# FPGA-Blitter.net
KiCad netlist of a schematic drawn in EAGLE
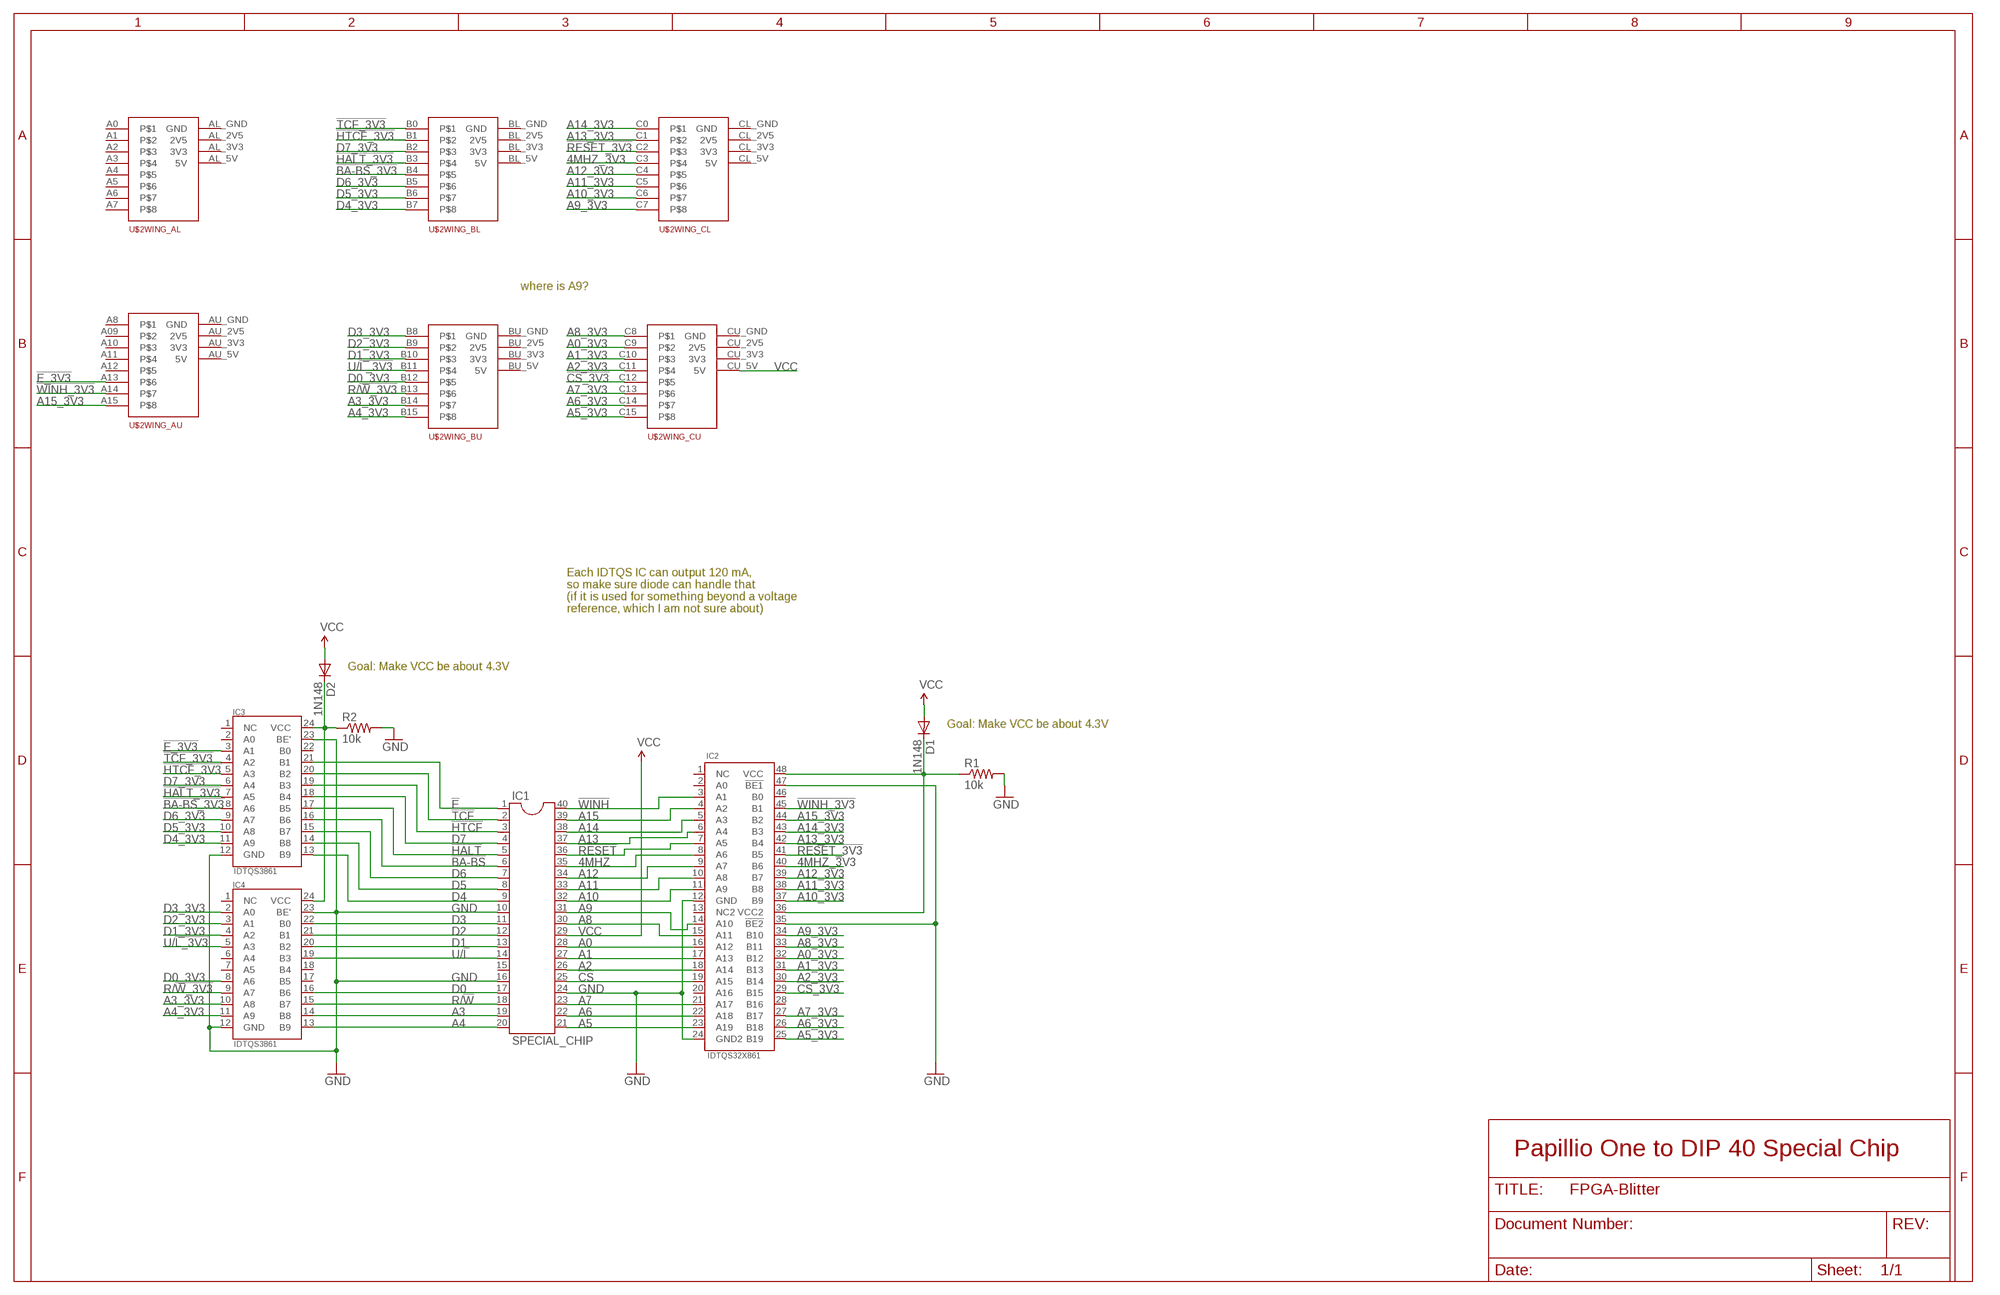
[diagram p0: schematic, sheet 1]

(export (version "E")
  (design (tool "Eeschema 10.0.6"))
  (components
    (comp (ref "D1")
      (value "1N148")
      (footprint "eagle-import:DIODE-1N4148")
      (libsource (lib "eagle-import") (part "DIODE1N4148"))
    )
    (comp (ref "D2")
      (value "1N148")
      (footprint "eagle-import:DIODE-1N4148")
      (libsource (lib "eagle-import") (part "DIODE1N4148"))
    )
    (comp (ref "IC1")
      (value "SPECIAL_CHIP")
      (footprint "eagle-import:DIL40")
      (libsource (lib "eagle-import") (part "DIL40"))
    )
    (comp (ref "IC2")
      (value "IDTQS32X861")
      (footprint "eagle-import:QVSOP-DJG48-IDT")
      (libsource (lib "eagle-import") (part "IDTQS32X861"))
    )
    (comp (ref "IC3")
      (value "IDTQS3861")
      (footprint "eagle-import:TSSOP24")
      (libsource (lib "eagle-import") (part "IDTQS3861"))
    )
    (comp (ref "IC4")
      (value "IDTQS3861")
      (footprint "eagle-import:TSSOP24")
      (libsource (lib "eagle-import") (part "IDTQS3861"))
    )
    (comp (ref "R1")
      (value "10k")
      (footprint "eagle-import:1206")
      (libsource (lib "eagle-import") (part "RESISTOR1206"))
    )
    (comp (ref "R2")
      (value "10k")
      (footprint "eagle-import:1206")
      (libsource (lib "eagle-import") (part "RESISTOR1206"))
    )
    (comp (ref "U$2")
      (value "PAPILIO48")
      (footprint "eagle-import:PAPILIO48")
      (libsource (lib "eagle-import") (part "PAPILIO48"))
    )
  )
  (nets
    (net (code "1") (name "/4MHZ") (class "Default")
      (node (ref "IC1") (pin "35") (pinfunction "35_35") (pintype "passive"))
      (node (ref "IC2") (pin "8") (pinfunction "A6_8") (pintype "bidirectional"))
    )
    (net (code "2") (name "/4MHZ_3V3") (class "Default")
      (node (ref "IC2") (pin "40") (pinfunction "B6_40") (pintype "bidirectional"))
      (node (ref "U$2") (pin "C3") (pinfunction "P$4_C3") (pintype "bidirectional"))
    )
    (net (code "3") (name "/A0") (class "Default")
      (node (ref "IC1") (pin "28") (pinfunction "28_28") (pintype "passive"))
      (node (ref "IC2") (pin "16") (pinfunction "A12_16") (pintype "bidirectional"))
    )
    (net (code "4") (name "/A0_3V3") (class "Default")
      (node (ref "IC2") (pin "32") (pinfunction "B12_32") (pintype "bidirectional"))
      (node (ref "U$2") (pin "C9") (pinfunction "P$2_C9") (pintype "bidirectional"))
    )
    (net (code "5") (name "/A1") (class "Default")
      (node (ref "IC1") (pin "27") (pinfunction "27_27") (pintype "passive"))
      (node (ref "IC2") (pin "17") (pinfunction "A13_17") (pintype "bidirectional"))
    )
    (net (code "6") (name "/A1_3V3") (class "Default")
      (node (ref "IC2") (pin "31") (pinfunction "B13_31") (pintype "bidirectional"))
      (node (ref "U$2") (pin "C10") (pinfunction "P$3_C10") (pintype "bidirectional"))
    )
    (net (code "7") (name "/A2") (class "Default")
      (node (ref "IC1") (pin "26") (pinfunction "26_26") (pintype "passive"))
      (node (ref "IC2") (pin "18") (pinfunction "A14_18") (pintype "bidirectional"))
    )
    (net (code "8") (name "/A2_3V3") (class "Default")
      (node (ref "IC2") (pin "30") (pinfunction "B14_30") (pintype "bidirectional"))
      (node (ref "U$2") (pin "C11") (pinfunction "P$4_C11") (pintype "bidirectional"))
    )
    (net (code "9") (name "/A3") (class "Default")
      (node (ref "IC1") (pin "19") (pinfunction "19_19") (pintype "passive"))
      (node (ref "IC4") (pin "14") (pinfunction "B8_14") (pintype "bidirectional"))
    )
    (net (code "10") (name "/A3_3V3") (class "Default")
      (node (ref "IC4") (pin "10") (pinfunction "A8_10") (pintype "bidirectional"))
      (node (ref "U$2") (pin "B14") (pinfunction "P$7_B14") (pintype "bidirectional"))
    )
    (net (code "11") (name "/A4") (class "Default")
      (node (ref "IC1") (pin "20") (pinfunction "20_20") (pintype "passive"))
      (node (ref "IC4") (pin "13") (pinfunction "B9_13") (pintype "bidirectional"))
    )
    (net (code "12") (name "/A4_3V3") (class "Default")
      (node (ref "IC4") (pin "11") (pinfunction "A9_11") (pintype "bidirectional"))
      (node (ref "U$2") (pin "B15") (pinfunction "P$8_B15") (pintype "bidirectional"))
    )
    (net (code "13") (name "/A5") (class "Default")
      (node (ref "IC1") (pin "21") (pinfunction "21_21") (pintype "passive"))
      (node (ref "IC2") (pin "23") (pinfunction "A19_23") (pintype "bidirectional"))
    )
    (net (code "14") (name "/A5_3V3") (class "Default")
      (node (ref "IC2") (pin "25") (pinfunction "B19_25") (pintype "bidirectional"))
      (node (ref "U$2") (pin "C15") (pinfunction "P$8_C15") (pintype "bidirectional"))
    )
    (net (code "15") (name "/A6") (class "Default")
      (node (ref "IC1") (pin "22") (pinfunction "22_22") (pintype "passive"))
      (node (ref "IC2") (pin "22") (pinfunction "A18_22") (pintype "bidirectional"))
    )
    (net (code "16") (name "/A6_3V3") (class "Default")
      (node (ref "IC2") (pin "26") (pinfunction "B18_26") (pintype "bidirectional"))
      (node (ref "U$2") (pin "C14") (pinfunction "P$7_C14") (pintype "bidirectional"))
    )
    (net (code "17") (name "/A7") (class "Default")
      (node (ref "IC1") (pin "23") (pinfunction "23_23") (pintype "passive"))
      (node (ref "IC2") (pin "21") (pinfunction "A17_21") (pintype "bidirectional"))
    )
    (net (code "18") (name "/A7_3V3") (class "Default")
      (node (ref "IC2") (pin "27") (pinfunction "B17_27") (pintype "bidirectional"))
      (node (ref "U$2") (pin "C13") (pinfunction "P$6_C13") (pintype "bidirectional"))
    )
    (net (code "19") (name "/A8") (class "Default")
      (node (ref "IC1") (pin "30") (pinfunction "30_30") (pintype "passive"))
      (node (ref "IC2") (pin "15") (pinfunction "A11_15") (pintype "bidirectional"))
    )
    (net (code "20") (name "/A8_3V3") (class "Default")
      (node (ref "IC2") (pin "33") (pinfunction "B11_33") (pintype "bidirectional"))
      (node (ref "U$2") (pin "C8") (pinfunction "P$1_C8") (pintype "bidirectional"))
    )
    (net (code "21") (name "/A9") (class "Default")
      (node (ref "IC1") (pin "31") (pinfunction "31_31") (pintype "passive"))
      (node (ref "IC2") (pin "14") (pinfunction "A10_14") (pintype "bidirectional"))
    )
    (net (code "22") (name "/A9_3V3") (class "Default")
      (node (ref "IC2") (pin "34") (pinfunction "B10_34") (pintype "bidirectional"))
      (node (ref "U$2") (pin "C7") (pinfunction "P$8_C7") (pintype "bidirectional"))
    )
    (net (code "23") (name "/A10") (class "Default")
      (node (ref "IC1") (pin "32") (pinfunction "32_32") (pintype "passive"))
      (node (ref "IC2") (pin "11") (pinfunction "A9_11") (pintype "bidirectional"))
    )
    (net (code "24") (name "/A10_3V3") (class "Default")
      (node (ref "IC2") (pin "37") (pinfunction "B9_37") (pintype "bidirectional"))
      (node (ref "U$2") (pin "C6") (pinfunction "P$7_C6") (pintype "bidirectional"))
    )
    (net (code "25") (name "/A11") (class "Default")
      (node (ref "IC1") (pin "33") (pinfunction "33_33") (pintype "passive"))
      (node (ref "IC2") (pin "10") (pinfunction "A8_10") (pintype "bidirectional"))
    )
    (net (code "26") (name "/A11_3V3") (class "Default")
      (node (ref "IC2") (pin "38") (pinfunction "B8_38") (pintype "bidirectional"))
      (node (ref "U$2") (pin "C5") (pinfunction "P$6_C5") (pintype "bidirectional"))
    )
    (net (code "27") (name "/A12") (class "Default")
      (node (ref "IC1") (pin "34") (pinfunction "34_34") (pintype "passive"))
      (node (ref "IC2") (pin "9") (pinfunction "A7_9") (pintype "bidirectional"))
    )
    (net (code "28") (name "/A12_3V3") (class "Default")
      (node (ref "IC2") (pin "39") (pinfunction "B7_39") (pintype "bidirectional"))
      (node (ref "U$2") (pin "C4") (pinfunction "P$5_C4") (pintype "bidirectional"))
    )
    (net (code "29") (name "/A13") (class "Default")
      (node (ref "IC1") (pin "37") (pinfunction "37_37") (pintype "passive"))
      (node (ref "IC2") (pin "6") (pinfunction "A4_6") (pintype "bidirectional"))
    )
    (net (code "30") (name "/A13_3V3") (class "Default")
      (node (ref "IC2") (pin "42") (pinfunction "B4_42") (pintype "bidirectional"))
      (node (ref "U$2") (pin "C1") (pinfunction "P$2_C1") (pintype "bidirectional"))
    )
    (net (code "31") (name "/A14") (class "Default")
      (node (ref "IC1") (pin "38") (pinfunction "38_38") (pintype "passive"))
      (node (ref "IC2") (pin "5") (pinfunction "A3_5") (pintype "bidirectional"))
    )
    (net (code "32") (name "/A14_3V3") (class "Default")
      (node (ref "IC2") (pin "43") (pinfunction "B3_43") (pintype "bidirectional"))
      (node (ref "U$2") (pin "C0") (pinfunction "P$1_C0") (pintype "bidirectional"))
    )
    (net (code "33") (name "/A15") (class "Default")
      (node (ref "IC1") (pin "39") (pinfunction "39_39") (pintype "passive"))
      (node (ref "IC2") (pin "4") (pinfunction "A2_4") (pintype "bidirectional"))
    )
    (net (code "34") (name "/A15_3V3") (class "Default")
      (node (ref "IC2") (pin "44") (pinfunction "B2_44") (pintype "bidirectional"))
      (node (ref "U$2") (pin "A15") (pinfunction "P$8_A15") (pintype "bidirectional"))
    )
    (net (code "35") (name "/D0") (class "Default")
      (node (ref "IC1") (pin "17") (pinfunction "17_17") (pintype "passive"))
      (node (ref "IC4") (pin "16") (pinfunction "B6_16") (pintype "bidirectional"))
    )
    (net (code "36") (name "/D0_3V3") (class "Default")
      (node (ref "IC4") (pin "8") (pinfunction "A6_8") (pintype "bidirectional"))
      (node (ref "U$2") (pin "B12") (pinfunction "P$5_B12") (pintype "bidirectional"))
    )
    (net (code "37") (name "/D1") (class "Default")
      (node (ref "IC1") (pin "13") (pinfunction "13_13") (pintype "passive"))
      (node (ref "IC4") (pin "20") (pinfunction "B2_20") (pintype "bidirectional"))
    )
    (net (code "38") (name "/D1_3V3") (class "Default")
      (node (ref "IC4") (pin "4") (pinfunction "A2_4") (pintype "bidirectional"))
      (node (ref "U$2") (pin "B10") (pinfunction "P$3_B10") (pintype "bidirectional"))
    )
    (net (code "39") (name "/D2") (class "Default")
      (node (ref "IC1") (pin "12") (pinfunction "12_12") (pintype "passive"))
      (node (ref "IC4") (pin "21") (pinfunction "B1_21") (pintype "bidirectional"))
    )
    (net (code "40") (name "/D2_3V3") (class "Default")
      (node (ref "IC4") (pin "3") (pinfunction "A1_3") (pintype "bidirectional"))
      (node (ref "U$2") (pin "B9") (pinfunction "P$2_B9") (pintype "bidirectional"))
    )
    (net (code "41") (name "/D3") (class "Default")
      (node (ref "IC1") (pin "11") (pinfunction "11_11") (pintype "passive"))
      (node (ref "IC4") (pin "22") (pinfunction "B0_22") (pintype "bidirectional"))
    )
    (net (code "42") (name "/D3_3V3") (class "Default")
      (node (ref "IC4") (pin "2") (pinfunction "A0_2") (pintype "bidirectional"))
      (node (ref "U$2") (pin "B8") (pinfunction "P$1_B8") (pintype "bidirectional"))
    )
    (net (code "43") (name "/D4") (class "Default")
      (node (ref "IC1") (pin "9") (pinfunction "9_9") (pintype "passive"))
      (node (ref "IC3") (pin "13") (pinfunction "B9_13") (pintype "bidirectional"))
    )
    (net (code "44") (name "/D4_3V3") (class "Default")
      (node (ref "IC3") (pin "11") (pinfunction "A9_11") (pintype "bidirectional"))
      (node (ref "U$2") (pin "B7") (pinfunction "P$8_B7") (pintype "bidirectional"))
    )
    (net (code "45") (name "/D5") (class "Default")
      (node (ref "IC1") (pin "8") (pinfunction "8_8") (pintype "passive"))
      (node (ref "IC3") (pin "14") (pinfunction "B8_14") (pintype "bidirectional"))
    )
    (net (code "46") (name "/D5_3V3") (class "Default")
      (node (ref "IC3") (pin "10") (pinfunction "A8_10") (pintype "bidirectional"))
      (node (ref "U$2") (pin "B6") (pinfunction "P$7_B6") (pintype "bidirectional"))
    )
    (net (code "47") (name "/D6") (class "Default")
      (node (ref "IC1") (pin "7") (pinfunction "7_7") (pintype "passive"))
      (node (ref "IC3") (pin "15") (pinfunction "B7_15") (pintype "bidirectional"))
    )
    (net (code "48") (name "/D6_3V3") (class "Default")
      (node (ref "IC3") (pin "9") (pinfunction "A7_9") (pintype "bidirectional"))
      (node (ref "U$2") (pin "B5") (pinfunction "P$6_B5") (pintype "bidirectional"))
    )
    (net (code "49") (name "/D7") (class "Default")
      (node (ref "IC1") (pin "4") (pinfunction "4_4") (pintype "passive"))
      (node (ref "IC3") (pin "18") (pinfunction "B4_18") (pintype "bidirectional"))
    )
    (net (code "50") (name "/D7_3V3") (class "Default")
      (node (ref "IC3") (pin "6") (pinfunction "A4_6") (pintype "bidirectional"))
      (node (ref "U$2") (pin "B2") (pinfunction "P$3_B2") (pintype "bidirectional"))
    )
    (net (code "51") (name "/R{slash}~{W_3V3}") (class "Default")
      (node (ref "IC4") (pin "9") (pinfunction "A7_9") (pintype "bidirectional"))
      (node (ref "U$2") (pin "B13") (pinfunction "P$6_B13") (pintype "bidirectional"))
    )
    (net (code "52") (name "/R{slash}~{W}") (class "Default")
      (node (ref "IC1") (pin "18") (pinfunction "18_18") (pintype "passive"))
      (node (ref "IC4") (pin "15") (pinfunction "B7_15") (pintype "bidirectional"))
    )
    (net (code "53") (name "/U{slash}~{L_3V3}") (class "Default")
      (node (ref "IC4") (pin "5") (pinfunction "A3_5") (pintype "bidirectional"))
      (node (ref "U$2") (pin "B11") (pinfunction "P$4_B11") (pintype "bidirectional"))
    )
    (net (code "54") (name "/U{slash}~{L}") (class "Default")
      (node (ref "IC1") (pin "14") (pinfunction "14_14") (pintype "passive"))
      (node (ref "IC4") (pin "19") (pinfunction "B3_19") (pintype "bidirectional"))
    )
    (net (code "55") (name "/~{BA-BS_3V3}") (class "Default")
      (node (ref "IC3") (pin "8") (pinfunction "A6_8") (pintype "bidirectional"))
      (node (ref "U$2") (pin "B4") (pinfunction "P$5_B4") (pintype "bidirectional"))
    )
    (net (code "56") (name "/~{BA-BS}") (class "Default")
      (node (ref "IC1") (pin "6") (pinfunction "6_6") (pintype "passive"))
      (node (ref "IC3") (pin "16") (pinfunction "B6_16") (pintype "bidirectional"))
    )
    (net (code "57") (name "/~{CS_3V3}") (class "Default")
      (node (ref "IC2") (pin "29") (pinfunction "B15_29") (pintype "bidirectional"))
      (node (ref "U$2") (pin "C12") (pinfunction "P$5_C12") (pintype "bidirectional"))
    )
    (net (code "58") (name "/~{CS}") (class "Default")
      (node (ref "IC1") (pin "25") (pinfunction "25_25") (pintype "passive"))
      (node (ref "IC2") (pin "19") (pinfunction "A15_19") (pintype "bidirectional"))
    )
    (net (code "59") (name "/~{E_3V3}") (class "Default")
      (node (ref "IC3") (pin "3") (pinfunction "A1_3") (pintype "bidirectional"))
      (node (ref "U$2") (pin "A13") (pinfunction "P$6_A13") (pintype "bidirectional"))
    )
    (net (code "60") (name "/~{E}") (class "Default")
      (node (ref "IC1") (pin "1") (pinfunction "1_1") (pintype "passive"))
      (node (ref "IC3") (pin "21") (pinfunction "B1_21") (pintype "bidirectional"))
    )
    (net (code "61") (name "/~{HALT_3V3}") (class "Default")
      (node (ref "IC3") (pin "7") (pinfunction "A5_7") (pintype "bidirectional"))
      (node (ref "U$2") (pin "B3") (pinfunction "P$4_B3") (pintype "bidirectional"))
    )
    (net (code "62") (name "/~{HALT}") (class "Default")
      (node (ref "IC1") (pin "5") (pinfunction "5_5") (pintype "passive"))
      (node (ref "IC3") (pin "17") (pinfunction "B5_17") (pintype "bidirectional"))
    )
    (net (code "63") (name "/~{HTCF_3V3}") (class "Default")
      (node (ref "IC3") (pin "5") (pinfunction "A3_5") (pintype "bidirectional"))
      (node (ref "U$2") (pin "B1") (pinfunction "P$2_B1") (pintype "bidirectional"))
    )
    (net (code "64") (name "/~{HTCF}") (class "Default")
      (node (ref "IC1") (pin "3") (pinfunction "3_3") (pintype "passive"))
      (node (ref "IC3") (pin "19") (pinfunction "B3_19") (pintype "bidirectional"))
    )
    (net (code "65") (name "/~{RESET_3V3}") (class "Default")
      (node (ref "IC2") (pin "41") (pinfunction "B5_41") (pintype "bidirectional"))
      (node (ref "U$2") (pin "C2") (pinfunction "P$3_C2") (pintype "bidirectional"))
    )
    (net (code "66") (name "/~{RESET}") (class "Default")
      (node (ref "IC1") (pin "36") (pinfunction "36_36") (pintype "passive"))
      (node (ref "IC2") (pin "7") (pinfunction "A5_7") (pintype "bidirectional"))
    )
    (net (code "67") (name "/~{TCF_3V3}") (class "Default")
      (node (ref "IC3") (pin "4") (pinfunction "A2_4") (pintype "bidirectional"))
      (node (ref "U$2") (pin "B0") (pinfunction "P$1_B0") (pintype "bidirectional"))
    )
    (net (code "68") (name "/~{TCF}") (class "Default")
      (node (ref "IC1") (pin "2") (pinfunction "2_2") (pintype "passive"))
      (node (ref "IC3") (pin "20") (pinfunction "B2_20") (pintype "bidirectional"))
    )
    (net (code "69") (name "/~{WINH_3V3}") (class "Default")
      (node (ref "IC2") (pin "45") (pinfunction "B1_45") (pintype "bidirectional"))
      (node (ref "U$2") (pin "A14") (pinfunction "P$7_A14") (pintype "bidirectional"))
    )
    (net (code "70") (name "/~{WINH}") (class "Default")
      (node (ref "IC1") (pin "40") (pinfunction "40_40") (pintype "passive"))
      (node (ref "IC2") (pin "3") (pinfunction "A1_3") (pintype "bidirectional"))
    )
    (net (code "71") (name "GND") (class "Default")
      (node (ref "IC1") (pin "10") (pinfunction "10_10") (pintype "passive"))
      (node (ref "IC1") (pin "16") (pinfunction "16_16") (pintype "passive"))
      (node (ref "IC1") (pin "24") (pinfunction "24_24") (pintype "passive"))
      (node (ref "IC2") (pin "12") (pinfunction "GND_12") (pintype "bidirectional"))
      (node (ref "IC2") (pin "24") (pinfunction "GND2_24") (pintype "bidirectional"))
      (node (ref "IC2") (pin "35") (pinfunction "~{BE2}_35") (pintype "bidirectional"))
      (node (ref "IC2") (pin "47") (pinfunction "~{BE1}_47") (pintype "bidirectional"))
      (node (ref "IC3") (pin "12") (pinfunction "GND_12") (pintype "bidirectional"))
      (node (ref "IC3") (pin "23") (pinfunction "BE'_23") (pintype "bidirectional"))
      (node (ref "IC4") (pin "12") (pinfunction "GND_12") (pintype "bidirectional"))
      (node (ref "IC4") (pin "23") (pinfunction "BE'_23") (pintype "bidirectional"))
      (node (ref "R1") (pin "2") (pinfunction "2_2") (pintype "passive"))
      (node (ref "R2") (pin "2") (pinfunction "2_2") (pintype "passive"))
    )
    (net (code "72") (name "Net-(IC2-VCC)") (class "Default")
      (node (ref "D1") (pin "C") (pinfunction "C_C") (pintype "passive"))
      (node (ref "IC2") (pin "36") (pinfunction "VCC2_36") (pintype "bidirectional"))
      (node (ref "IC2") (pin "48") (pinfunction "VCC_48") (pintype "bidirectional"))
      (node (ref "R1") (pin "1") (pinfunction "1_1") (pintype "passive"))
    )
    (net (code "73") (name "Net-(IC3-VCC)") (class "Default")
      (node (ref "D2") (pin "C") (pinfunction "C_C") (pintype "passive"))
      (node (ref "IC3") (pin "24") (pinfunction "VCC_24") (pintype "bidirectional"))
      (node (ref "IC4") (pin "24") (pinfunction "VCC_24") (pintype "bidirectional"))
      (node (ref "R2") (pin "1") (pinfunction "1_1") (pintype "passive"))
    )
    (net (code "74") (name "VCC") (class "Default")
      (node (ref "D1") (pin "A") (pinfunction "A_A") (pintype "passive"))
      (node (ref "D2") (pin "A") (pinfunction "A_A") (pintype "passive"))
      (node (ref "IC1") (pin "29") (pinfunction "29_29") (pintype "passive"))
      (node (ref "U$2") (pin "CU_5V") (pinfunction "5V_CU_5V") (pintype "bidirectional"))
    )
    (net (code "75") (name "unconnected-(IC1-Pad15)") (class "Default")
      (node (ref "IC1") (pin "15") (pinfunction "15_15") (pintype "passive"))
    )
    (net (code "76") (name "unconnected-(IC2-A0-Pad2)") (class "Default")
      (node (ref "IC2") (pin "2") (pinfunction "A0_2") (pintype "bidirectional"))
    )
    (net (code "77") (name "unconnected-(IC2-A16-Pad20)") (class "Default")
      (node (ref "IC2") (pin "20") (pinfunction "A16_20") (pintype "bidirectional"))
    )
    (net (code "78") (name "unconnected-(IC2-B0-Pad46)") (class "Default")
      (node (ref "IC2") (pin "46") (pinfunction "B0_46") (pintype "bidirectional"))
    )
    (net (code "79") (name "unconnected-(IC2-B16-Pad28)") (class "Default")
      (node (ref "IC2") (pin "28") (pinfunction "B16_28") (pintype "bidirectional"))
    )
    (net (code "80") (name "unconnected-(IC2-NC-Pad1)") (class "Default")
      (node (ref "IC2") (pin "1") (pinfunction "NC_1") (pintype "bidirectional"))
    )
    (net (code "81") (name "unconnected-(IC2-NC2-Pad13)") (class "Default")
      (node (ref "IC2") (pin "13") (pinfunction "NC2_13") (pintype "bidirectional"))
    )
    (net (code "82") (name "unconnected-(IC3-A0-Pad2)") (class "Default")
      (node (ref "IC3") (pin "2") (pinfunction "A0_2") (pintype "bidirectional"))
    )
    (net (code "83") (name "unconnected-(IC3-B0-Pad22)") (class "Default")
      (node (ref "IC3") (pin "22") (pinfunction "B0_22") (pintype "bidirectional"))
    )
    (net (code "84") (name "unconnected-(IC3-NC-Pad1)") (class "Default")
      (node (ref "IC3") (pin "1") (pinfunction "NC_1") (pintype "bidirectional"))
    )
    (net (code "85") (name "unconnected-(IC4-A4-Pad6)") (class "Default")
      (node (ref "IC4") (pin "6") (pinfunction "A4_6") (pintype "bidirectional"))
    )
    (net (code "86") (name "unconnected-(IC4-A5-Pad7)") (class "Default")
      (node (ref "IC4") (pin "7") (pinfunction "A5_7") (pintype "bidirectional"))
    )
    (net (code "87") (name "unconnected-(IC4-B4-Pad18)") (class "Default")
      (node (ref "IC4") (pin "18") (pinfunction "B4_18") (pintype "bidirectional"))
    )
    (net (code "88") (name "unconnected-(IC4-B5-Pad17)") (class "Default")
      (node (ref "IC4") (pin "17") (pinfunction "B5_17") (pintype "bidirectional"))
    )
    (net (code "89") (name "unconnected-(IC4-NC-Pad1)") (class "Default")
      (node (ref "IC4") (pin "1") (pinfunction "NC_1") (pintype "bidirectional"))
    )
    (net (code "90") (name "unconnected-(U$2A-2V5-PadAL_2V5)") (class "Default")
      (node (ref "U$2") (pin "AL_2V5") (pinfunction "2V5_AL_2V5") (pintype "bidirectional"))
    )
    (net (code "91") (name "unconnected-(U$2A-3V3-PadAL_3V3)") (class "Default")
      (node (ref "U$2") (pin "AL_3V3") (pinfunction "3V3_AL_3V3") (pintype "bidirectional"))
    )
    (net (code "92") (name "unconnected-(U$2A-5V-PadAL_5V)") (class "Default")
      (node (ref "U$2") (pin "AL_5V") (pinfunction "5V_AL_5V") (pintype "bidirectional"))
    )
    (net (code "93") (name "unconnected-(U$2A-GND-PadAL_GND)") (class "Default")
      (node (ref "U$2") (pin "AL_GND") (pinfunction "GND_AL_GND") (pintype "bidirectional"))
    )
    (net (code "94") (name "unconnected-(U$2A-P$1-PadA0)") (class "Default")
      (node (ref "U$2") (pin "A0") (pinfunction "P$1_A0") (pintype "bidirectional"))
    )
    (net (code "95") (name "unconnected-(U$2A-P$2-PadA1)") (class "Default")
      (node (ref "U$2") (pin "A1") (pinfunction "P$2_A1") (pintype "bidirectional"))
    )
    (net (code "96") (name "unconnected-(U$2A-P$3-PadA2)") (class "Default")
      (node (ref "U$2") (pin "A2") (pinfunction "P$3_A2") (pintype "bidirectional"))
    )
    (net (code "97") (name "unconnected-(U$2A-P$4-PadA3)") (class "Default")
      (node (ref "U$2") (pin "A3") (pinfunction "P$4_A3") (pintype "bidirectional"))
    )
    (net (code "98") (name "unconnected-(U$2A-P$5-PadA4)") (class "Default")
      (node (ref "U$2") (pin "A4") (pinfunction "P$5_A4") (pintype "bidirectional"))
    )
    (net (code "99") (name "unconnected-(U$2A-P$6-PadA5)") (class "Default")
      (node (ref "U$2") (pin "A5") (pinfunction "P$6_A5") (pintype "bidirectional"))
    )
    (net (code "100") (name "unconnected-(U$2A-P$7-PadA6)") (class "Default")
      (node (ref "U$2") (pin "A6") (pinfunction "P$7_A6") (pintype "bidirectional"))
    )
    (net (code "101") (name "unconnected-(U$2A-P$8-PadA7)") (class "Default")
      (node (ref "U$2") (pin "A7") (pinfunction "P$8_A7") (pintype "bidirectional"))
    )
    (net (code "102") (name "unconnected-(U$2B-2V5-PadAU_2V5)") (class "Default")
      (node (ref "U$2") (pin "AU_2V5") (pinfunction "2V5_AU_2V5") (pintype "bidirectional"))
    )
    (net (code "103") (name "unconnected-(U$2B-3V3-PadAU_3V3)") (class "Default")
      (node (ref "U$2") (pin "AU_3V3") (pinfunction "3V3_AU_3V3") (pintype "bidirectional"))
    )
    (net (code "104") (name "unconnected-(U$2B-5V-PadAU_5V)") (class "Default")
      (node (ref "U$2") (pin "AU_5V") (pinfunction "5V_AU_5V") (pintype "bidirectional"))
    )
    (net (code "105") (name "unconnected-(U$2B-GND-PadAU_GND)") (class "Default")
      (node (ref "U$2") (pin "AU_GND") (pinfunction "GND_AU_GND") (pintype "bidirectional"))
    )
    (net (code "106") (name "unconnected-(U$2B-P$1-PadA8)") (class "Default")
      (node (ref "U$2") (pin "A8") (pinfunction "P$1_A8") (pintype "bidirectional"))
    )
    (net (code "107") (name "unconnected-(U$2B-P$2-PadA09)") (class "Default")
      (node (ref "U$2") (pin "A09") (pinfunction "P$2_A09") (pintype "bidirectional"))
    )
    (net (code "108") (name "unconnected-(U$2B-P$3-PadA10)") (class "Default")
      (node (ref "U$2") (pin "A10") (pinfunction "P$3_A10") (pintype "bidirectional"))
    )
    (net (code "109") (name "unconnected-(U$2B-P$4-PadA11)") (class "Default")
      (node (ref "U$2") (pin "A11") (pinfunction "P$4_A11") (pintype "bidirectional"))
    )
    (net (code "110") (name "unconnected-(U$2B-P$5-PadA12)") (class "Default")
      (node (ref "U$2") (pin "A12") (pinfunction "P$5_A12") (pintype "bidirectional"))
    )
    (net (code "111") (name "unconnected-(U$2C-2V5-PadBL_2V5)") (class "Default")
      (node (ref "U$2") (pin "BL_2V5") (pinfunction "2V5_BL_2V5") (pintype "bidirectional"))
    )
    (net (code "112") (name "unconnected-(U$2C-3V3-PadBL_3V3)") (class "Default")
      (node (ref "U$2") (pin "BL_3V3") (pinfunction "3V3_BL_3V3") (pintype "bidirectional"))
    )
    (net (code "113") (name "unconnected-(U$2C-5V-PadBL_5V)") (class "Default")
      (node (ref "U$2") (pin "BL_5V") (pinfunction "5V_BL_5V") (pintype "bidirectional"))
    )
    (net (code "114") (name "unconnected-(U$2C-GND-PadBL_GND)") (class "Default")
      (node (ref "U$2") (pin "BL_GND") (pinfunction "GND_BL_GND") (pintype "bidirectional"))
    )
    (net (code "115") (name "unconnected-(U$2D-2V5-PadBU_2V5)") (class "Default")
      (node (ref "U$2") (pin "BU_2V5") (pinfunction "2V5_BU_2V5") (pintype "bidirectional"))
    )
    (net (code "116") (name "unconnected-(U$2D-3V3-PadBU_3V3)") (class "Default")
      (node (ref "U$2") (pin "BU_3V3") (pinfunction "3V3_BU_3V3") (pintype "bidirectional"))
    )
    (net (code "117") (name "unconnected-(U$2D-5V-PadBU_5V)") (class "Default")
      (node (ref "U$2") (pin "BU_5V") (pinfunction "5V_BU_5V") (pintype "bidirectional"))
    )
    (net (code "118") (name "unconnected-(U$2D-GND-PadBU_GND)") (class "Default")
      (node (ref "U$2") (pin "BU_GND") (pinfunction "GND_BU_GND") (pintype "bidirectional"))
    )
    (net (code "119") (name "unconnected-(U$2E-2V5-PadCL_2V5)") (class "Default")
      (node (ref "U$2") (pin "CL_2V5") (pinfunction "2V5_CL_2V5") (pintype "bidirectional"))
    )
    (net (code "120") (name "unconnected-(U$2E-3V3-PadCL_3V3)") (class "Default")
      (node (ref "U$2") (pin "CL_3V3") (pinfunction "3V3_CL_3V3") (pintype "bidirectional"))
    )
    (net (code "121") (name "unconnected-(U$2E-5V-PadCL_5V)") (class "Default")
      (node (ref "U$2") (pin "CL_5V") (pinfunction "5V_CL_5V") (pintype "bidirectional"))
    )
    (net (code "122") (name "unconnected-(U$2E-GND-PadCL_GND)") (class "Default")
      (node (ref "U$2") (pin "CL_GND") (pinfunction "GND_CL_GND") (pintype "bidirectional"))
    )
    (net (code "123") (name "unconnected-(U$2F-2V5-PadCU_2V5)") (class "Default")
      (node (ref "U$2") (pin "CU_2V5") (pinfunction "2V5_CU_2V5") (pintype "bidirectional"))
    )
    (net (code "124") (name "unconnected-(U$2F-3V3-PadCU_3V3)") (class "Default")
      (node (ref "U$2") (pin "CU_3V3") (pinfunction "3V3_CU_3V3") (pintype "bidirectional"))
    )
    (net (code "125") (name "unconnected-(U$2F-GND-PadCU_GND)") (class "Default")
      (node (ref "U$2") (pin "CU_GND") (pinfunction "GND_CU_GND") (pintype "bidirectional"))
    )
  )
)
